# Grove_-_Infrared_Reflective_Sensor.net
KiCad netlist of a schematic drawn in EAGLE
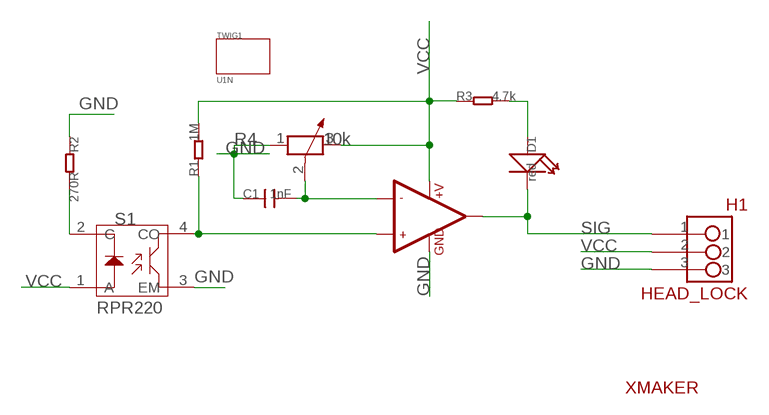
[diagram p0: schematic, sheet 1]

(export (version "E")
  (design (tool "Eeschema 10.0.6"))
  (components
    (comp (ref "C1")
      (value "1nF")
      (footprint "eagle-import:0603")
      (libsource (lib "eagle-import") (part "C-0603"))
    )
    (comp (ref "D1")
      (value "red")
      (footprint "eagle-import:LED0603")
      (libsource (lib "eagle-import") (part "007-LED3540"))
    )
    (comp (ref "H1")
      (value "HEAD_LOCK")
      (footprint "eagle-import:HEAD_LOCK")
      (libsource (lib "eagle-import") (part "HEAD_LOCK"))
    )
    (comp (ref "R1")
      (value "1M")
      (footprint "eagle-import:0603_S")
      (libsource (lib "eagle-import") (part "005-R0603_S"))
    )
    (comp (ref "R2")
      (value "270R")
      (footprint "eagle-import:0603_S")
      (libsource (lib "eagle-import") (part "005-R0603_S"))
    )
    (comp (ref "R3")
      (value "4.7k")
      (footprint "eagle-import:0603_S")
      (libsource (lib "eagle-import") (part "005-R0603_S"))
    )
    (comp (ref "R4")
      (value "10k")
      (footprint "eagle-import:3P-SQUA-6.7X6.4")
      (libsource (lib "eagle-import") (part "R-POTENTIOMETEREVN-D8A-A03-B"))
    )
    (comp (ref "S1")
      (value "RPR220")
      (footprint "eagle-import:4P-6.4X4.9X6.5H")
      (libsource (lib "eagle-import") (part "REFLECTIVE-PHOTOSENSOR-RPR-220"))
    )
    (comp (ref "TWIG1")
      (value "U1N")
      (footprint "eagle-import:U1N")
      (libsource (lib "eagle-import") (part "U1N"))
    )
    (comp (ref "U$3")
      (value "XMAKERLOGO2")
      (footprint "eagle-import:XMAKERLOGO2")
      (libsource (lib "eagle-import") (part "XMAKERLOGO2"))
    )
    (comp (ref "U1")
      (value "002-LMV358")
      (footprint "eagle-import:SO08")
      (libsource (lib "eagle-import") (part "002-LMV358"))
    )
  )
  (nets
    (net (code "1") (name "/GND") (class "Default")
      (node (ref "C1") (pin "1") (pinfunction "1_1") (pintype "passive"))
      (node (ref "H1") (pin "3") (pinfunction "3_3") (pintype "passive"))
      (node (ref "R2") (pin "1") (pinfunction "1_1") (pintype "passive"))
      (node (ref "R4") (pin "1") (pinfunction "1_1") (pintype "passive"))
      (node (ref "S1") (pin "3") (pinfunction "EM_3") (pintype "bidirectional"))
      (node (ref "U1") (pin "4") (pinfunction "GND_4") (pintype "power_in"))
    )
    (net (code "2") (name "/SIG") (class "Default")
      (node (ref "D1") (pin "2") (pinfunction "-_2") (pintype "passive"))
      (node (ref "H1") (pin "1") (pinfunction "1_1") (pintype "passive"))
      (node (ref "U1") (pin "1") (pinfunction "OUT1_1") (pintype "output"))
    )
    (net (code "3") (name "/VCC") (class "Default")
      (node (ref "H1") (pin "2") (pinfunction "2_2") (pintype "passive"))
      (node (ref "R1") (pin "2") (pinfunction "2_2") (pintype "passive"))
      (node (ref "R3") (pin "1") (pinfunction "1_1") (pintype "passive"))
      (node (ref "R4") (pin "3") (pinfunction "2_3") (pintype "passive"))
      (node (ref "S1") (pin "1") (pinfunction "A_1") (pintype "bidirectional"))
      (node (ref "U1") (pin "8") (pinfunction "+V_8") (pintype "power_in"))
    )
    (net (code "4") (name "Net-(D1-+)") (class "Default")
      (node (ref "D1") (pin "1") (pinfunction "+_1") (pintype "passive"))
      (node (ref "R3") (pin "2") (pinfunction "2_2") (pintype "passive"))
    )
    (net (code "5") (name "Net-(R4-3)") (class "Default")
      (node (ref "C1") (pin "2") (pinfunction "2_2") (pintype "passive"))
      (node (ref "R4") (pin "2") (pinfunction "3_2") (pintype "passive"))
      (node (ref "U1") (pin "2") (pinfunction "-IN1_2") (pintype "input"))
    )
    (net (code "6") (name "Net-(S1-C)") (class "Default")
      (node (ref "R2") (pin "2") (pinfunction "2_2") (pintype "passive"))
      (node (ref "S1") (pin "2") (pinfunction "C_2") (pintype "bidirectional"))
    )
    (net (code "7") (name "Net-(S1-CO)") (class "Default")
      (node (ref "R1") (pin "1") (pinfunction "1_1") (pintype "passive"))
      (node (ref "S1") (pin "4") (pinfunction "CO_4") (pintype "bidirectional"))
      (node (ref "U1") (pin "3") (pinfunction "+IN1_3") (pintype "input"))
    )
  )
)
